# Nixieclock.net
KiCad netlist of a schematic drawn in EAGLE
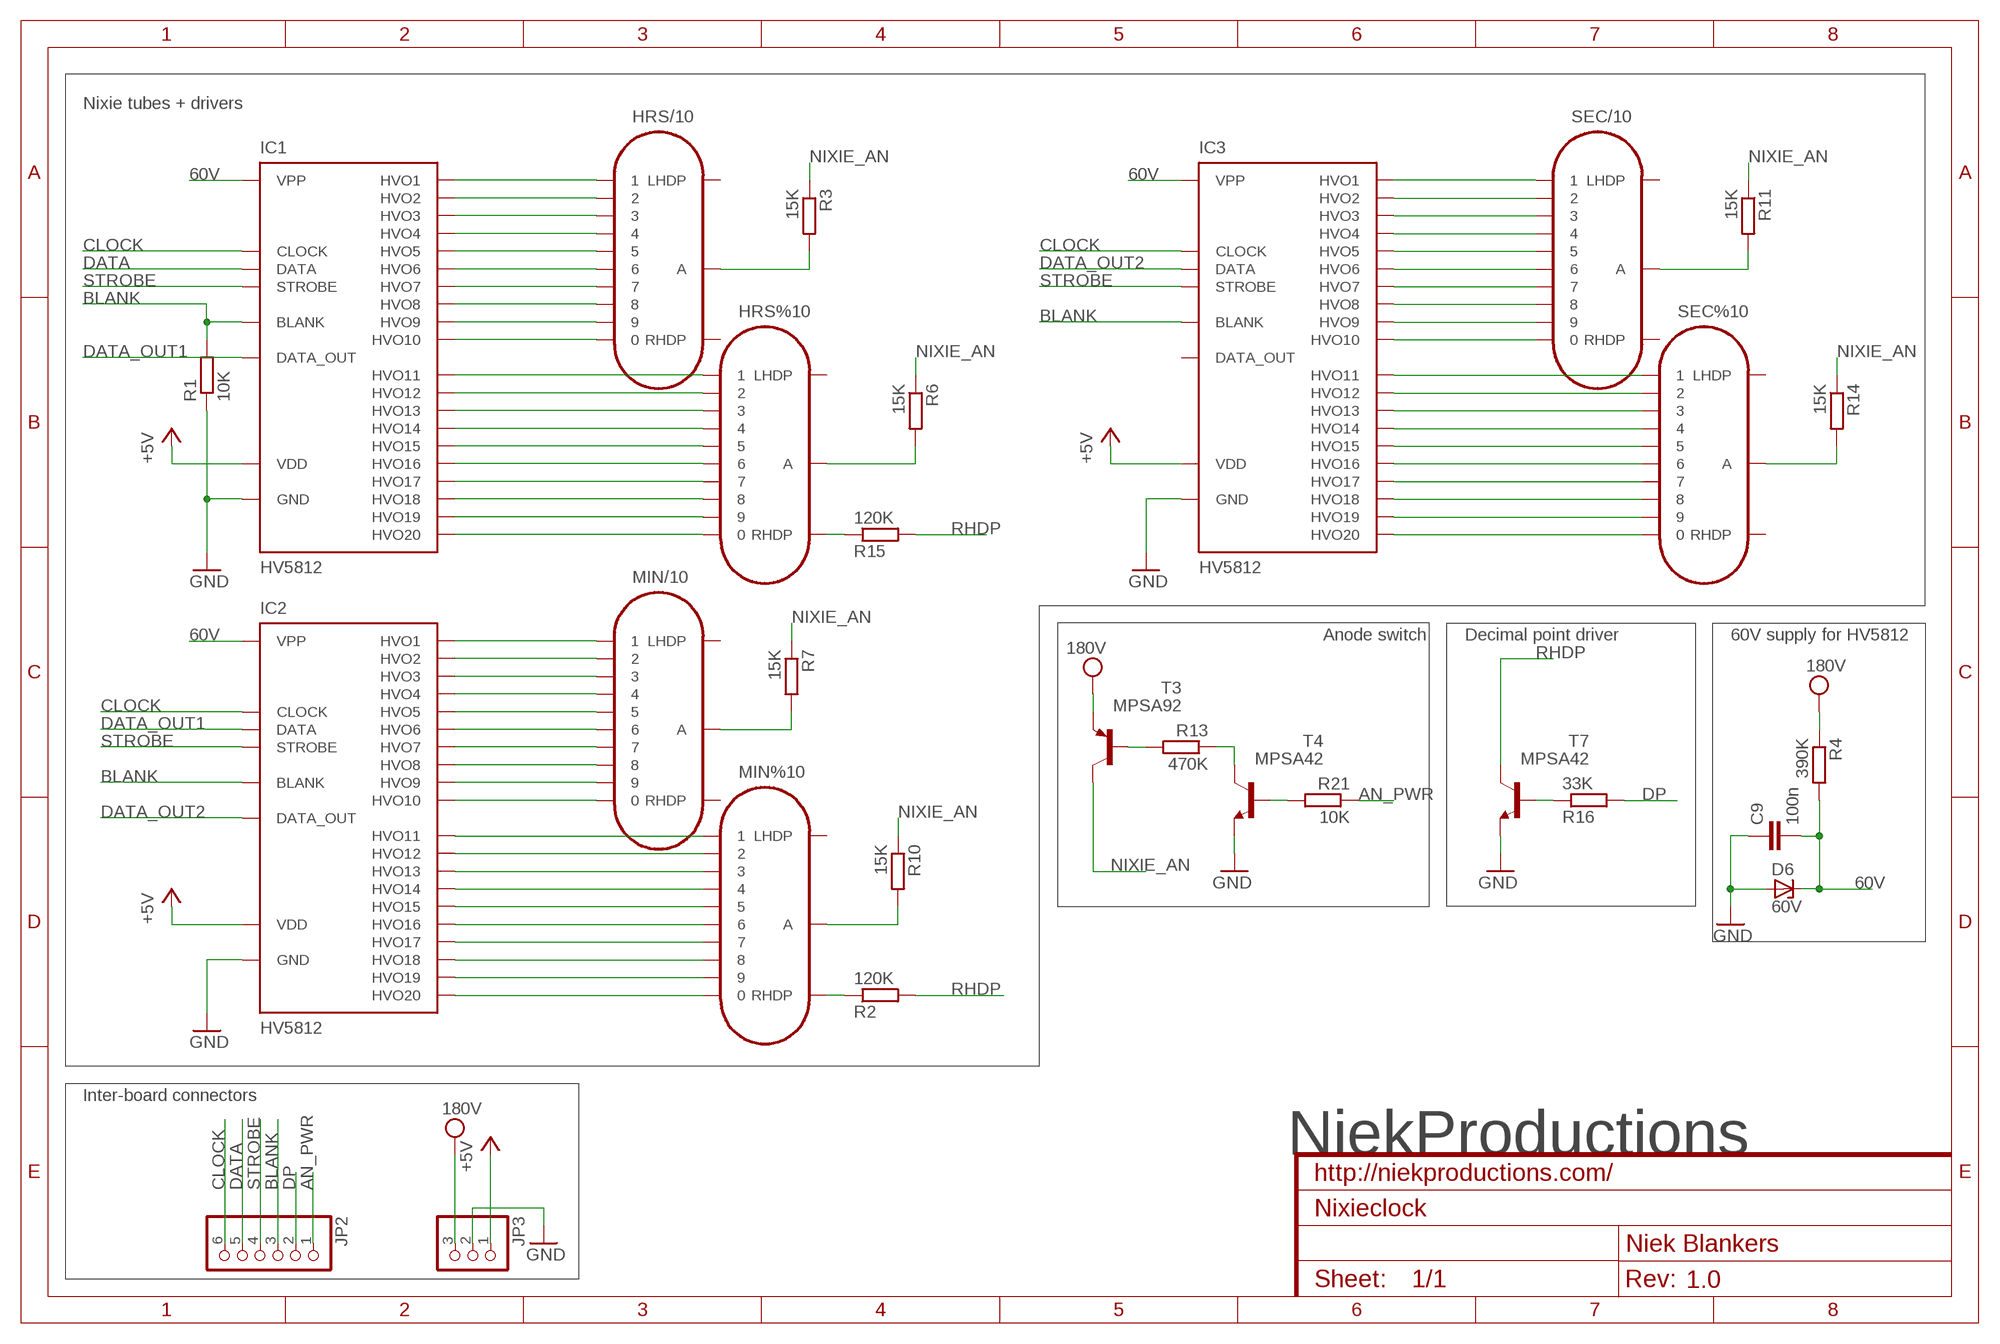
[diagram p0: schematic, sheet 1]

(export (version "E")
  (design (tool "Eeschema 10.0.6"))
  (components
    (comp (ref "C9")
      (value "100n")
      (footprint "eagle-import:C025-025X050")
      (libsource (lib "eagle-import") (part "C-EU025-025X050"))
    )
    (comp (ref "D6")
      (value "60V")
      (footprint "eagle-import:F126Z12")
      (libsource (lib "eagle-import") (part "ZENER-DIODEF126-12"))
    )
    (comp (ref "HRS%10")
      (value "IN-14")
      (footprint "eagle-import:IN-14")
      (libsource (lib "eagle-import") (part "IN-14"))
    )
    (comp (ref "HRS/10")
      (value "IN-14")
      (footprint "eagle-import:IN-14")
      (libsource (lib "eagle-import") (part "IN-14"))
    )
    (comp (ref "IC1")
      (value "HV5812")
      (footprint "eagle-import:PLCC-28-SMD")
      (libsource (lib "eagle-import") (part "HV5812"))
    )
    (comp (ref "IC2")
      (value "HV5812")
      (footprint "eagle-import:PLCC-28-SMD")
      (libsource (lib "eagle-import") (part "HV5812"))
    )
    (comp (ref "IC3")
      (value "HV5812")
      (footprint "eagle-import:PLCC-28-SMD")
      (libsource (lib "eagle-import") (part "HV5812"))
    )
    (comp (ref "JP2")
      (value "PINHD-1X6")
      (footprint "eagle-import:1X06")
      (libsource (lib "eagle-import") (part "PINHD-1X6"))
    )
    (comp (ref "JP3")
      (value "PINHD-1X3")
      (footprint "eagle-import:1X03")
      (libsource (lib "eagle-import") (part "PINHD-1X3"))
    )
    (comp (ref "MIN%10")
      (value "IN-14")
      (footprint "eagle-import:IN-14")
      (libsource (lib "eagle-import") (part "IN-14"))
    )
    (comp (ref "MIN/10")
      (value "IN-14")
      (footprint "eagle-import:IN-14")
      (libsource (lib "eagle-import") (part "IN-14"))
    )
    (comp (ref "R1")
      (value "10K")
      (footprint "eagle-import:0207_12")
      (libsource (lib "eagle-import") (part "R-EU_0207/12"))
    )
    (comp (ref "R2")
      (value "120K")
      (footprint "eagle-import:0207_12")
      (libsource (lib "eagle-import") (part "R-EU_0207/12"))
    )
    (comp (ref "R3")
      (value "15K")
      (footprint "eagle-import:0207_12")
      (libsource (lib "eagle-import") (part "R-EU_0207/12"))
    )
    (comp (ref "R4")
      (value "390K")
      (footprint "eagle-import:0207_12")
      (libsource (lib "eagle-import") (part "R-EU_0207/12"))
    )
    (comp (ref "R6")
      (value "15K")
      (footprint "eagle-import:0207_12")
      (libsource (lib "eagle-import") (part "R-EU_0207/12"))
    )
    (comp (ref "R7")
      (value "15K")
      (footprint "eagle-import:0207_12")
      (libsource (lib "eagle-import") (part "R-EU_0207/12"))
    )
    (comp (ref "R10")
      (value "15K")
      (footprint "eagle-import:0207_12")
      (libsource (lib "eagle-import") (part "R-EU_0207/12"))
    )
    (comp (ref "R11")
      (value "15K")
      (footprint "eagle-import:0207_12")
      (libsource (lib "eagle-import") (part "R-EU_0207/12"))
    )
    (comp (ref "R13")
      (value "470K")
      (footprint "eagle-import:0207_12")
      (libsource (lib "eagle-import") (part "R-EU_0207/12"))
    )
    (comp (ref "R14")
      (value "15K")
      (footprint "eagle-import:0207_12")
      (libsource (lib "eagle-import") (part "R-EU_0207/12"))
    )
    (comp (ref "R15")
      (value "120K")
      (footprint "eagle-import:0207_12")
      (libsource (lib "eagle-import") (part "R-EU_0207/12"))
    )
    (comp (ref "R16")
      (value "33K")
      (footprint "eagle-import:0207_12")
      (libsource (lib "eagle-import") (part "R-EU_0207/12"))
    )
    (comp (ref "R21")
      (value "10K")
      (footprint "eagle-import:0207_12")
      (libsource (lib "eagle-import") (part "R-EU_0207/12"))
    )
    (comp (ref "SEC%10")
      (value "IN-14")
      (footprint "eagle-import:IN-14")
      (libsource (lib "eagle-import") (part "IN-14"))
    )
    (comp (ref "SEC/10")
      (value "IN-14")
      (footprint "eagle-import:IN-14")
      (libsource (lib "eagle-import") (part "IN-14"))
    )
    (comp (ref "T3")
      (value "MPSA92")
      (footprint "eagle-import:TO92-EBC")
      (libsource (lib "eagle-import") (part "-PNP-TO92-EBCMPSA92"))
    )
    (comp (ref "T4")
      (value "MPSA42")
      (footprint "eagle-import:TO92-EBC")
      (libsource (lib "eagle-import") (part "-NPN-TO92-EBC"))
    )
    (comp (ref "T7")
      (value "MPSA42")
      (footprint "eagle-import:TO92-EBC")
      (libsource (lib "eagle-import") (part "-NPN-TO92-EBC"))
    )
    (comp (ref "U$4")
      (value "NPLOGO1CM-DIA")
      (footprint "eagle-import:NPLOGO-1CM")
      (libsource (lib "eagle-import") (part "NPLOGO1CM-DIA"))
    )
  )
  (nets
    (net (code "1") (name "+5V") (class "Default")
      (node (ref "IC1") (pin "28") (pinfunction "VDD_28") (pintype "power_in"))
      (node (ref "IC2") (pin "28") (pinfunction "VDD_28") (pintype "power_in"))
      (node (ref "IC3") (pin "28") (pinfunction "VDD_28") (pintype "power_in"))
      (node (ref "JP3") (pin "1") (pinfunction "1_1") (pintype "passive"))
    )
    (net (code "2") (name "/60V") (class "Default")
      (node (ref "C9") (pin "2") (pinfunction "2_2") (pintype "passive"))
      (node (ref "D6") (pin "C") (pinfunction "C_C") (pintype "passive"))
      (node (ref "IC1") (pin "1") (pinfunction "VPP_1") (pintype "power_in"))
      (node (ref "IC2") (pin "1") (pinfunction "VPP_1") (pintype "power_in"))
      (node (ref "IC3") (pin "1") (pinfunction "VPP_1") (pintype "power_in"))
      (node (ref "R4") (pin "2") (pinfunction "2_2") (pintype "passive"))
    )
    (net (code "3") (name "/AN_PWR") (class "Default")
      (node (ref "JP2") (pin "1") (pinfunction "1_1") (pintype "passive"))
      (node (ref "R21") (pin "1") (pinfunction "1_1") (pintype "passive"))
    )
    (net (code "4") (name "/BLANK") (class "Default")
      (node (ref "IC1") (pin "13") (pinfunction "BLANK_13") (pintype "input"))
      (node (ref "IC2") (pin "13") (pinfunction "BLANK_13") (pintype "input"))
      (node (ref "IC3") (pin "13") (pinfunction "BLANK_13") (pintype "input"))
      (node (ref "JP2") (pin "3") (pinfunction "3_3") (pintype "passive"))
      (node (ref "R1") (pin "2") (pinfunction "2_2") (pintype "passive"))
    )
    (net (code "5") (name "/CLOCK") (class "Default")
      (node (ref "IC1") (pin "15") (pinfunction "CLOCK_15") (pintype "input"))
      (node (ref "IC2") (pin "15") (pinfunction "CLOCK_15") (pintype "input"))
      (node (ref "IC3") (pin "15") (pinfunction "CLOCK_15") (pintype "input"))
      (node (ref "JP2") (pin "6") (pinfunction "6_6") (pintype "passive"))
    )
    (net (code "6") (name "/DATA") (class "Default")
      (node (ref "IC1") (pin "27") (pinfunction "DATA_27") (pintype "input"))
      (node (ref "JP2") (pin "5") (pinfunction "5_5") (pintype "passive"))
    )
    (net (code "7") (name "/DATA_OUT1") (class "Default")
      (node (ref "IC1") (pin "2") (pinfunction "DATA_OUT_2") (pintype "output"))
      (node (ref "IC2") (pin "27") (pinfunction "DATA_27") (pintype "input"))
    )
    (net (code "8") (name "/DATA_OUT2") (class "Default")
      (node (ref "IC2") (pin "2") (pinfunction "DATA_OUT_2") (pintype "output"))
      (node (ref "IC3") (pin "27") (pinfunction "DATA_27") (pintype "input"))
    )
    (net (code "9") (name "/DP") (class "Default")
      (node (ref "JP2") (pin "2") (pinfunction "2_2") (pintype "passive"))
      (node (ref "R16") (pin "2") (pinfunction "2_2") (pintype "passive"))
    )
    (net (code "10") (name "/NIXIE_AN") (class "Default")
      (node (ref "R10") (pin "1") (pinfunction "1_1") (pintype "passive"))
      (node (ref "R11") (pin "1") (pinfunction "1_1") (pintype "passive"))
      (node (ref "R14") (pin "1") (pinfunction "1_1") (pintype "passive"))
      (node (ref "R3") (pin "1") (pinfunction "1_1") (pintype "passive"))
      (node (ref "R6") (pin "1") (pinfunction "1_1") (pintype "passive"))
      (node (ref "R7") (pin "1") (pinfunction "1_1") (pintype "passive"))
      (node (ref "T3") (pin "C") (pinfunction "C_C") (pintype "passive"))
    )
    (net (code "11") (name "/RHDP") (class "Default")
      (node (ref "R15") (pin "2") (pinfunction "2_2") (pintype "passive"))
      (node (ref "R2") (pin "2") (pinfunction "2_2") (pintype "passive"))
      (node (ref "T7") (pin "C") (pinfunction "C_C") (pintype "passive"))
    )
    (net (code "12") (name "/STROBE") (class "Default")
      (node (ref "IC1") (pin "16") (pinfunction "STROBE_16") (pintype "input"))
      (node (ref "IC2") (pin "16") (pinfunction "STROBE_16") (pintype "input"))
      (node (ref "IC3") (pin "16") (pinfunction "STROBE_16") (pintype "input"))
      (node (ref "JP2") (pin "4") (pinfunction "4_4") (pintype "passive"))
    )
    (net (code "13") (name "180V") (class "Default")
      (node (ref "JP3") (pin "3") (pinfunction "3_3") (pintype "passive"))
      (node (ref "R4") (pin "1") (pinfunction "1_1") (pintype "passive"))
      (node (ref "T3") (pin "E") (pinfunction "E_E") (pintype "passive"))
    )
    (net (code "14") (name "GND") (class "Default")
      (node (ref "C9") (pin "1") (pinfunction "1_1") (pintype "passive"))
      (node (ref "D6") (pin "A") (pinfunction "A_A") (pintype "passive"))
      (node (ref "IC1") (pin "14") (pinfunction "GND_14") (pintype "power_in"))
      (node (ref "IC2") (pin "14") (pinfunction "GND_14") (pintype "power_in"))
      (node (ref "IC3") (pin "14") (pinfunction "GND_14") (pintype "power_in"))
      (node (ref "JP3") (pin "2") (pinfunction "2_2") (pintype "passive"))
      (node (ref "R1") (pin "1") (pinfunction "1_1") (pintype "passive"))
      (node (ref "T4") (pin "E") (pinfunction "E_E") (pintype "passive"))
      (node (ref "T7") (pin "E") (pinfunction "E_E") (pintype "passive"))
    )
    (net (code "15") (name "Net-(HRS%10-PadA)") (class "Default")
      (node (ref "HRS%10") (pin "A") (pinfunction "A_A") (pintype "bidirectional"))
      (node (ref "R6") (pin "2") (pinfunction "2_2") (pintype "passive"))
    )
    (net (code "16") (name "Net-(HRS%10-PadRHDP)") (class "Default")
      (node (ref "HRS%10") (pin "RHDP") (pinfunction "RHDP_RHDP") (pintype "bidirectional"))
      (node (ref "R15") (pin "1") (pinfunction "1_1") (pintype "passive"))
    )
    (net (code "17") (name "Net-(HRS/10-PadA)") (class "Default")
      (node (ref "HRS/10") (pin "A") (pinfunction "A_A") (pintype "bidirectional"))
      (node (ref "R3") (pin "2") (pinfunction "2_2") (pintype "passive"))
    )
    (net (code "18") (name "Net-(IC1-HVO1)") (class "Default")
      (node (ref "HRS/10") (pin "1") (pinfunction "1_1") (pintype "bidirectional"))
      (node (ref "IC1") (pin "26") (pinfunction "HVO1_26") (pintype "output"))
    )
    (net (code "19") (name "Net-(IC1-HVO2)") (class "Default")
      (node (ref "HRS/10") (pin "2") (pinfunction "2_2") (pintype "bidirectional"))
      (node (ref "IC1") (pin "25") (pinfunction "HVO2_25") (pintype "output"))
    )
    (net (code "20") (name "Net-(IC1-HVO3)") (class "Default")
      (node (ref "HRS/10") (pin "3") (pinfunction "3_3") (pintype "bidirectional"))
      (node (ref "IC1") (pin "24") (pinfunction "HVO3_24") (pintype "output"))
    )
    (net (code "21") (name "Net-(IC1-HVO4)") (class "Default")
      (node (ref "HRS/10") (pin "4") (pinfunction "4_4") (pintype "bidirectional"))
      (node (ref "IC1") (pin "23") (pinfunction "HVO4_23") (pintype "output"))
    )
    (net (code "22") (name "Net-(IC1-HVO5)") (class "Default")
      (node (ref "HRS/10") (pin "5") (pinfunction "5_5") (pintype "bidirectional"))
      (node (ref "IC1") (pin "22") (pinfunction "HVO5_22") (pintype "output"))
    )
    (net (code "23") (name "Net-(IC1-HVO6)") (class "Default")
      (node (ref "HRS/10") (pin "6") (pinfunction "6_6") (pintype "bidirectional"))
      (node (ref "IC1") (pin "21") (pinfunction "HVO6_21") (pintype "output"))
    )
    (net (code "24") (name "Net-(IC1-HVO7)") (class "Default")
      (node (ref "HRS/10") (pin "7") (pinfunction "7_7") (pintype "bidirectional"))
      (node (ref "IC1") (pin "20") (pinfunction "HVO7_20") (pintype "output"))
    )
    (net (code "25") (name "Net-(IC1-HVO8)") (class "Default")
      (node (ref "HRS/10") (pin "8") (pinfunction "8_8") (pintype "bidirectional"))
      (node (ref "IC1") (pin "19") (pinfunction "HVO8_19") (pintype "output"))
    )
    (net (code "26") (name "Net-(IC1-HVO9)") (class "Default")
      (node (ref "HRS/10") (pin "9") (pinfunction "9_9") (pintype "bidirectional"))
      (node (ref "IC1") (pin "18") (pinfunction "HVO9_18") (pintype "output"))
    )
    (net (code "27") (name "Net-(IC1-HVO10)") (class "Default")
      (node (ref "HRS/10") (pin "0") (pinfunction "0_0") (pintype "bidirectional"))
      (node (ref "IC1") (pin "17") (pinfunction "HVO10_17") (pintype "output"))
    )
    (net (code "28") (name "Net-(IC1-HVO11)") (class "Default")
      (node (ref "HRS%10") (pin "1") (pinfunction "1_1") (pintype "bidirectional"))
      (node (ref "IC1") (pin "12") (pinfunction "HVO11_12") (pintype "output"))
    )
    (net (code "29") (name "Net-(IC1-HVO12)") (class "Default")
      (node (ref "HRS%10") (pin "2") (pinfunction "2_2") (pintype "bidirectional"))
      (node (ref "IC1") (pin "11") (pinfunction "HVO12_11") (pintype "output"))
    )
    (net (code "30") (name "Net-(IC1-HVO13)") (class "Default")
      (node (ref "HRS%10") (pin "3") (pinfunction "3_3") (pintype "bidirectional"))
      (node (ref "IC1") (pin "10") (pinfunction "HVO13_10") (pintype "output"))
    )
    (net (code "31") (name "Net-(IC1-HVO14)") (class "Default")
      (node (ref "HRS%10") (pin "4") (pinfunction "4_4") (pintype "bidirectional"))
      (node (ref "IC1") (pin "9") (pinfunction "HVO14_9") (pintype "output"))
    )
    (net (code "32") (name "Net-(IC1-HVO15)") (class "Default")
      (node (ref "HRS%10") (pin "5") (pinfunction "5_5") (pintype "bidirectional"))
      (node (ref "IC1") (pin "8") (pinfunction "HVO15_8") (pintype "output"))
    )
    (net (code "33") (name "Net-(IC1-HVO16)") (class "Default")
      (node (ref "HRS%10") (pin "6") (pinfunction "6_6") (pintype "bidirectional"))
      (node (ref "IC1") (pin "7") (pinfunction "HVO16_7") (pintype "output"))
    )
    (net (code "34") (name "Net-(IC1-HVO17)") (class "Default")
      (node (ref "HRS%10") (pin "7") (pinfunction "7_7") (pintype "bidirectional"))
      (node (ref "IC1") (pin "6") (pinfunction "HVO17_6") (pintype "output"))
    )
    (net (code "35") (name "Net-(IC1-HVO18)") (class "Default")
      (node (ref "HRS%10") (pin "8") (pinfunction "8_8") (pintype "bidirectional"))
      (node (ref "IC1") (pin "5") (pinfunction "HVO18_5") (pintype "output"))
    )
    (net (code "36") (name "Net-(IC1-HVO19)") (class "Default")
      (node (ref "HRS%10") (pin "9") (pinfunction "9_9") (pintype "bidirectional"))
      (node (ref "IC1") (pin "4") (pinfunction "HVO19_4") (pintype "output"))
    )
    (net (code "37") (name "Net-(IC1-HVO20)") (class "Default")
      (node (ref "HRS%10") (pin "0") (pinfunction "0_0") (pintype "bidirectional"))
      (node (ref "IC1") (pin "3") (pinfunction "HVO20_3") (pintype "output"))
    )
    (net (code "38") (name "Net-(IC2-HVO1)") (class "Default")
      (node (ref "IC2") (pin "26") (pinfunction "HVO1_26") (pintype "output"))
      (node (ref "MIN/10") (pin "1") (pinfunction "1_1") (pintype "bidirectional"))
    )
    (net (code "39") (name "Net-(IC2-HVO2)") (class "Default")
      (node (ref "IC2") (pin "25") (pinfunction "HVO2_25") (pintype "output"))
      (node (ref "MIN/10") (pin "2") (pinfunction "2_2") (pintype "bidirectional"))
    )
    (net (code "40") (name "Net-(IC2-HVO3)") (class "Default")
      (node (ref "IC2") (pin "24") (pinfunction "HVO3_24") (pintype "output"))
      (node (ref "MIN/10") (pin "3") (pinfunction "3_3") (pintype "bidirectional"))
    )
    (net (code "41") (name "Net-(IC2-HVO4)") (class "Default")
      (node (ref "IC2") (pin "23") (pinfunction "HVO4_23") (pintype "output"))
      (node (ref "MIN/10") (pin "4") (pinfunction "4_4") (pintype "bidirectional"))
    )
    (net (code "42") (name "Net-(IC2-HVO5)") (class "Default")
      (node (ref "IC2") (pin "22") (pinfunction "HVO5_22") (pintype "output"))
      (node (ref "MIN/10") (pin "5") (pinfunction "5_5") (pintype "bidirectional"))
    )
    (net (code "43") (name "Net-(IC2-HVO6)") (class "Default")
      (node (ref "IC2") (pin "21") (pinfunction "HVO6_21") (pintype "output"))
      (node (ref "MIN/10") (pin "6") (pinfunction "6_6") (pintype "bidirectional"))
    )
    (net (code "44") (name "Net-(IC2-HVO7)") (class "Default")
      (node (ref "IC2") (pin "20") (pinfunction "HVO7_20") (pintype "output"))
      (node (ref "MIN/10") (pin "7") (pinfunction "7_7") (pintype "bidirectional"))
    )
    (net (code "45") (name "Net-(IC2-HVO8)") (class "Default")
      (node (ref "IC2") (pin "19") (pinfunction "HVO8_19") (pintype "output"))
      (node (ref "MIN/10") (pin "8") (pinfunction "8_8") (pintype "bidirectional"))
    )
    (net (code "46") (name "Net-(IC2-HVO9)") (class "Default")
      (node (ref "IC2") (pin "18") (pinfunction "HVO9_18") (pintype "output"))
      (node (ref "MIN/10") (pin "9") (pinfunction "9_9") (pintype "bidirectional"))
    )
    (net (code "47") (name "Net-(IC2-HVO10)") (class "Default")
      (node (ref "IC2") (pin "17") (pinfunction "HVO10_17") (pintype "output"))
      (node (ref "MIN/10") (pin "0") (pinfunction "0_0") (pintype "bidirectional"))
    )
    (net (code "48") (name "Net-(IC2-HVO11)") (class "Default")
      (node (ref "IC2") (pin "12") (pinfunction "HVO11_12") (pintype "output"))
      (node (ref "MIN%10") (pin "1") (pinfunction "1_1") (pintype "bidirectional"))
    )
    (net (code "49") (name "Net-(IC2-HVO12)") (class "Default")
      (node (ref "IC2") (pin "11") (pinfunction "HVO12_11") (pintype "output"))
      (node (ref "MIN%10") (pin "2") (pinfunction "2_2") (pintype "bidirectional"))
    )
    (net (code "50") (name "Net-(IC2-HVO13)") (class "Default")
      (node (ref "IC2") (pin "10") (pinfunction "HVO13_10") (pintype "output"))
      (node (ref "MIN%10") (pin "3") (pinfunction "3_3") (pintype "bidirectional"))
    )
    (net (code "51") (name "Net-(IC2-HVO14)") (class "Default")
      (node (ref "IC2") (pin "9") (pinfunction "HVO14_9") (pintype "output"))
      (node (ref "MIN%10") (pin "4") (pinfunction "4_4") (pintype "bidirectional"))
    )
    (net (code "52") (name "Net-(IC2-HVO15)") (class "Default")
      (node (ref "IC2") (pin "8") (pinfunction "HVO15_8") (pintype "output"))
      (node (ref "MIN%10") (pin "5") (pinfunction "5_5") (pintype "bidirectional"))
    )
    (net (code "53") (name "Net-(IC2-HVO16)") (class "Default")
      (node (ref "IC2") (pin "7") (pinfunction "HVO16_7") (pintype "output"))
      (node (ref "MIN%10") (pin "6") (pinfunction "6_6") (pintype "bidirectional"))
    )
    (net (code "54") (name "Net-(IC2-HVO17)") (class "Default")
      (node (ref "IC2") (pin "6") (pinfunction "HVO17_6") (pintype "output"))
      (node (ref "MIN%10") (pin "7") (pinfunction "7_7") (pintype "bidirectional"))
    )
    (net (code "55") (name "Net-(IC2-HVO18)") (class "Default")
      (node (ref "IC2") (pin "5") (pinfunction "HVO18_5") (pintype "output"))
      (node (ref "MIN%10") (pin "8") (pinfunction "8_8") (pintype "bidirectional"))
    )
    (net (code "56") (name "Net-(IC2-HVO19)") (class "Default")
      (node (ref "IC2") (pin "4") (pinfunction "HVO19_4") (pintype "output"))
      (node (ref "MIN%10") (pin "9") (pinfunction "9_9") (pintype "bidirectional"))
    )
    (net (code "57") (name "Net-(IC2-HVO20)") (class "Default")
      (node (ref "IC2") (pin "3") (pinfunction "HVO20_3") (pintype "output"))
      (node (ref "MIN%10") (pin "0") (pinfunction "0_0") (pintype "bidirectional"))
    )
    (net (code "58") (name "Net-(IC3-HVO1)") (class "Default")
      (node (ref "IC3") (pin "26") (pinfunction "HVO1_26") (pintype "output"))
      (node (ref "SEC/10") (pin "1") (pinfunction "1_1") (pintype "bidirectional"))
    )
    (net (code "59") (name "Net-(IC3-HVO2)") (class "Default")
      (node (ref "IC3") (pin "25") (pinfunction "HVO2_25") (pintype "output"))
      (node (ref "SEC/10") (pin "2") (pinfunction "2_2") (pintype "bidirectional"))
    )
    (net (code "60") (name "Net-(IC3-HVO3)") (class "Default")
      (node (ref "IC3") (pin "24") (pinfunction "HVO3_24") (pintype "output"))
      (node (ref "SEC/10") (pin "3") (pinfunction "3_3") (pintype "bidirectional"))
    )
    (net (code "61") (name "Net-(IC3-HVO4)") (class "Default")
      (node (ref "IC3") (pin "23") (pinfunction "HVO4_23") (pintype "output"))
      (node (ref "SEC/10") (pin "4") (pinfunction "4_4") (pintype "bidirectional"))
    )
    (net (code "62") (name "Net-(IC3-HVO5)") (class "Default")
      (node (ref "IC3") (pin "22") (pinfunction "HVO5_22") (pintype "output"))
      (node (ref "SEC/10") (pin "5") (pinfunction "5_5") (pintype "bidirectional"))
    )
    (net (code "63") (name "Net-(IC3-HVO6)") (class "Default")
      (node (ref "IC3") (pin "21") (pinfunction "HVO6_21") (pintype "output"))
      (node (ref "SEC/10") (pin "6") (pinfunction "6_6") (pintype "bidirectional"))
    )
    (net (code "64") (name "Net-(IC3-HVO7)") (class "Default")
      (node (ref "IC3") (pin "20") (pinfunction "HVO7_20") (pintype "output"))
      (node (ref "SEC/10") (pin "7") (pinfunction "7_7") (pintype "bidirectional"))
    )
    (net (code "65") (name "Net-(IC3-HVO8)") (class "Default")
      (node (ref "IC3") (pin "19") (pinfunction "HVO8_19") (pintype "output"))
      (node (ref "SEC/10") (pin "8") (pinfunction "8_8") (pintype "bidirectional"))
    )
    (net (code "66") (name "Net-(IC3-HVO9)") (class "Default")
      (node (ref "IC3") (pin "18") (pinfunction "HVO9_18") (pintype "output"))
      (node (ref "SEC/10") (pin "9") (pinfunction "9_9") (pintype "bidirectional"))
    )
    (net (code "67") (name "Net-(IC3-HVO10)") (class "Default")
      (node (ref "IC3") (pin "17") (pinfunction "HVO10_17") (pintype "output"))
      (node (ref "SEC/10") (pin "0") (pinfunction "0_0") (pintype "bidirectional"))
    )
    (net (code "68") (name "Net-(IC3-HVO11)") (class "Default")
      (node (ref "IC3") (pin "12") (pinfunction "HVO11_12") (pintype "output"))
      (node (ref "SEC%10") (pin "1") (pinfunction "1_1") (pintype "bidirectional"))
    )
    (net (code "69") (name "Net-(IC3-HVO12)") (class "Default")
      (node (ref "IC3") (pin "11") (pinfunction "HVO12_11") (pintype "output"))
      (node (ref "SEC%10") (pin "2") (pinfunction "2_2") (pintype "bidirectional"))
    )
    (net (code "70") (name "Net-(IC3-HVO13)") (class "Default")
      (node (ref "IC3") (pin "10") (pinfunction "HVO13_10") (pintype "output"))
      (node (ref "SEC%10") (pin "3") (pinfunction "3_3") (pintype "bidirectional"))
    )
    (net (code "71") (name "Net-(IC3-HVO14)") (class "Default")
      (node (ref "IC3") (pin "9") (pinfunction "HVO14_9") (pintype "output"))
      (node (ref "SEC%10") (pin "4") (pinfunction "4_4") (pintype "bidirectional"))
    )
    (net (code "72") (name "Net-(IC3-HVO15)") (class "Default")
      (node (ref "IC3") (pin "8") (pinfunction "HVO15_8") (pintype "output"))
      (node (ref "SEC%10") (pin "5") (pinfunction "5_5") (pintype "bidirectional"))
    )
    (net (code "73") (name "Net-(IC3-HVO16)") (class "Default")
      (node (ref "IC3") (pin "7") (pinfunction "HVO16_7") (pintype "output"))
      (node (ref "SEC%10") (pin "6") (pinfunction "6_6") (pintype "bidirectional"))
    )
    (net (code "74") (name "Net-(IC3-HVO17)") (class "Default")
      (node (ref "IC3") (pin "6") (pinfunction "HVO17_6") (pintype "output"))
      (node (ref "SEC%10") (pin "7") (pinfunction "7_7") (pintype "bidirectional"))
    )
    (net (code "75") (name "Net-(IC3-HVO18)") (class "Default")
      (node (ref "IC3") (pin "5") (pinfunction "HVO18_5") (pintype "output"))
      (node (ref "SEC%10") (pin "8") (pinfunction "8_8") (pintype "bidirectional"))
    )
    (net (code "76") (name "Net-(IC3-HVO19)") (class "Default")
      (node (ref "IC3") (pin "4") (pinfunction "HVO19_4") (pintype "output"))
      (node (ref "SEC%10") (pin "9") (pinfunction "9_9") (pintype "bidirectional"))
    )
    (net (code "77") (name "Net-(IC3-HVO20)") (class "Default")
      (node (ref "IC3") (pin "3") (pinfunction "HVO20_3") (pintype "output"))
      (node (ref "SEC%10") (pin "0") (pinfunction "0_0") (pintype "bidirectional"))
    )
    (net (code "78") (name "Net-(MIN%10-PadA)") (class "Default")
      (node (ref "MIN%10") (pin "A") (pinfunction "A_A") (pintype "bidirectional"))
      (node (ref "R10") (pin "2") (pinfunction "2_2") (pintype "passive"))
    )
    (net (code "79") (name "Net-(MIN%10-PadRHDP)") (class "Default")
      (node (ref "MIN%10") (pin "RHDP") (pinfunction "RHDP_RHDP") (pintype "bidirectional"))
      (node (ref "R2") (pin "1") (pinfunction "1_1") (pintype "passive"))
    )
    (net (code "80") (name "Net-(MIN/10-PadA)") (class "Default")
      (node (ref "MIN/10") (pin "A") (pinfunction "A_A") (pintype "bidirectional"))
      (node (ref "R7") (pin "2") (pinfunction "2_2") (pintype "passive"))
    )
    (net (code "81") (name "Net-(R11-Pad2)") (class "Default")
      (node (ref "R11") (pin "2") (pinfunction "2_2") (pintype "passive"))
      (node (ref "SEC/10") (pin "A") (pinfunction "A_A") (pintype "bidirectional"))
    )
    (net (code "82") (name "Net-(R13-Pad1)") (class "Default")
      (node (ref "R13") (pin "1") (pinfunction "1_1") (pintype "passive"))
      (node (ref "T4") (pin "C") (pinfunction "C_C") (pintype "passive"))
    )
    (net (code "83") (name "Net-(R13-Pad2)") (class "Default")
      (node (ref "R13") (pin "2") (pinfunction "2_2") (pintype "passive"))
      (node (ref "T3") (pin "B") (pinfunction "B_B") (pintype "passive"))
    )
    (net (code "84") (name "Net-(R14-Pad2)") (class "Default")
      (node (ref "R14") (pin "2") (pinfunction "2_2") (pintype "passive"))
      (node (ref "SEC%10") (pin "A") (pinfunction "A_A") (pintype "bidirectional"))
    )
    (net (code "85") (name "Net-(R16-Pad1)") (class "Default")
      (node (ref "R16") (pin "1") (pinfunction "1_1") (pintype "passive"))
      (node (ref "T7") (pin "B") (pinfunction "B_B") (pintype "passive"))
    )
    (net (code "86") (name "Net-(R21-Pad2)") (class "Default")
      (node (ref "R21") (pin "2") (pinfunction "2_2") (pintype "passive"))
      (node (ref "T4") (pin "B") (pinfunction "B_B") (pintype "passive"))
    )
    (net (code "87") (name "unconnected-(HRS%10-PadLHDP)") (class "Default")
      (node (ref "HRS%10") (pin "LHDP") (pinfunction "LHDP_LHDP") (pintype "bidirectional"))
    )
    (net (code "88") (name "unconnected-(HRS/10-PadLHDP)") (class "Default")
      (node (ref "HRS/10") (pin "LHDP") (pinfunction "LHDP_LHDP") (pintype "bidirectional"))
    )
    (net (code "89") (name "unconnected-(HRS/10-PadRHDP)") (class "Default")
      (node (ref "HRS/10") (pin "RHDP") (pinfunction "RHDP_RHDP") (pintype "bidirectional"))
    )
    (net (code "90") (name "unconnected-(IC3-DATA_OUT-Pad2)") (class "Default")
      (node (ref "IC3") (pin "2") (pinfunction "DATA_OUT_2") (pintype "output"))
    )
    (net (code "91") (name "unconnected-(MIN%10-PadLHDP)") (class "Default")
      (node (ref "MIN%10") (pin "LHDP") (pinfunction "LHDP_LHDP") (pintype "bidirectional"))
    )
    (net (code "92") (name "unconnected-(MIN/10-PadLHDP)") (class "Default")
      (node (ref "MIN/10") (pin "LHDP") (pinfunction "LHDP_LHDP") (pintype "bidirectional"))
    )
    (net (code "93") (name "unconnected-(MIN/10-PadRHDP)") (class "Default")
      (node (ref "MIN/10") (pin "RHDP") (pinfunction "RHDP_RHDP") (pintype "bidirectional"))
    )
    (net (code "94") (name "unconnected-(SEC%10-PadLHDP)") (class "Default")
      (node (ref "SEC%10") (pin "LHDP") (pinfunction "LHDP_LHDP") (pintype "bidirectional"))
    )
    (net (code "95") (name "unconnected-(SEC%10-PadRHDP)") (class "Default")
      (node (ref "SEC%10") (pin "RHDP") (pinfunction "RHDP_RHDP") (pintype "bidirectional"))
    )
    (net (code "96") (name "unconnected-(SEC/10-PadLHDP)") (class "Default")
      (node (ref "SEC/10") (pin "LHDP") (pinfunction "LHDP_LHDP") (pintype "bidirectional"))
    )
    (net (code "97") (name "unconnected-(SEC/10-PadRHDP)") (class "Default")
      (node (ref "SEC/10") (pin "RHDP") (pinfunction "RHDP_RHDP") (pintype "bidirectional"))
    )
  )
)
